# KonamiSCC_Replacement.net
KiCad netlist of a schematic drawn in EAGLE
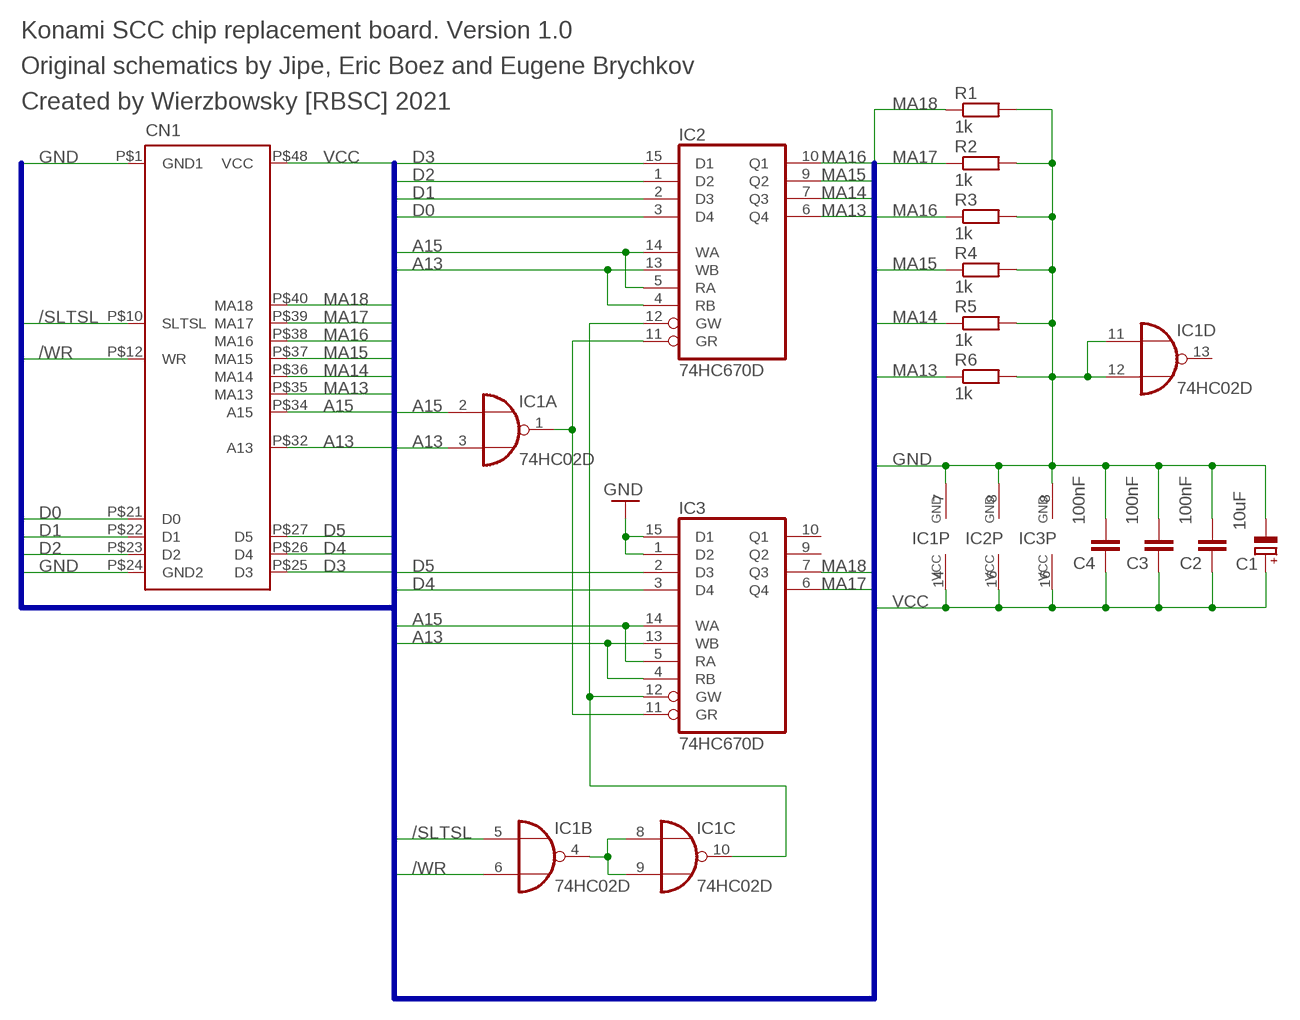
[diagram p0: schematic, sheet 1]

(export (version "E")
  (design (tool "Eeschema 10.0.6"))
  (components
    (comp (ref "C1")
      (value "10uF")
      (footprint "eagle-import:SMC_C")
      (libsource (lib "eagle-import") (part "CPOL-EUSMCC"))
    )
    (comp (ref "C2")
      (value "100nF")
      (footprint "eagle-import:C0805")
      (libsource (lib "eagle-import") (part "C-EUC0805"))
    )
    (comp (ref "C3")
      (value "100nF")
      (footprint "eagle-import:C0805")
      (libsource (lib "eagle-import") (part "C-EUC0805"))
    )
    (comp (ref "C4")
      (value "100nF")
      (footprint "eagle-import:C0805")
      (libsource (lib "eagle-import") (part "C-EUC0805"))
    )
    (comp (ref "CN1")
      (value "2212P003_PLACEHOLDERP")
      (footprint "eagle-import:DIP48")
      (libsource (lib "eagle-import") (part "2212P003_PLACEHOLDERP"))
    )
    (comp (ref "IC1")
      (value "74HC02D")
      (footprint "eagle-import:SO14")
      (libsource (lib "eagle-import") (part "7402DHC"))
    )
    (comp (ref "IC2")
      (value "74HC670D")
      (footprint "eagle-import:SO16")
      (libsource (lib "eagle-import") (part "74670DHC"))
    )
    (comp (ref "IC3")
      (value "74HC670D")
      (footprint "eagle-import:SO16")
      (libsource (lib "eagle-import") (part "74670DHC"))
    )
    (comp (ref "R1")
      (value "1k")
      (footprint "eagle-import:M0805")
      (libsource (lib "eagle-import") (part "R-EU_M0805"))
    )
    (comp (ref "R2")
      (value "1k")
      (footprint "eagle-import:M0805")
      (libsource (lib "eagle-import") (part "R-EU_M0805"))
    )
    (comp (ref "R3")
      (value "1k")
      (footprint "eagle-import:M0805")
      (libsource (lib "eagle-import") (part "R-EU_M0805"))
    )
    (comp (ref "R4")
      (value "1k")
      (footprint "eagle-import:M0805")
      (libsource (lib "eagle-import") (part "R-EU_M0805"))
    )
    (comp (ref "R5")
      (value "1k")
      (footprint "eagle-import:M0805")
      (libsource (lib "eagle-import") (part "R-EU_M0805"))
    )
    (comp (ref "R6")
      (value "1k")
      (footprint "eagle-import:M0805")
      (libsource (lib "eagle-import") (part "R-EU_M0805"))
    )
  )
  (nets
    (net (code "1") (name "/A13") (class "Default")
      (node (ref "CN1") (pin "P$32") (pinfunction "A13_P$32") (pintype "bidirectional"))
      (node (ref "IC1") (pin "3") (pinfunction "I1_3") (pintype "input"))
      (node (ref "IC2") (pin "13") (pinfunction "WB_13") (pintype "input"))
      (node (ref "IC2") (pin "4") (pinfunction "RB_4") (pintype "input"))
      (node (ref "IC3") (pin "13") (pinfunction "WB_13") (pintype "input"))
      (node (ref "IC3") (pin "4") (pinfunction "RB_4") (pintype "input"))
    )
    (net (code "2") (name "/A15") (class "Default")
      (node (ref "CN1") (pin "P$34") (pinfunction "A15_P$34") (pintype "bidirectional"))
      (node (ref "IC1") (pin "2") (pinfunction "I0_2") (pintype "input"))
      (node (ref "IC2") (pin "14") (pinfunction "WA_14") (pintype "input"))
      (node (ref "IC2") (pin "5") (pinfunction "RA_5") (pintype "input"))
      (node (ref "IC3") (pin "14") (pinfunction "WA_14") (pintype "input"))
      (node (ref "IC3") (pin "5") (pinfunction "RA_5") (pintype "input"))
    )
    (net (code "3") (name "/D0") (class "Default")
      (node (ref "CN1") (pin "P$21") (pinfunction "D0_P$21") (pintype "bidirectional"))
      (node (ref "IC2") (pin "3") (pinfunction "D4_3") (pintype "input"))
    )
    (net (code "4") (name "/D1") (class "Default")
      (node (ref "CN1") (pin "P$22") (pinfunction "D1_P$22") (pintype "bidirectional"))
      (node (ref "IC2") (pin "2") (pinfunction "D3_2") (pintype "input"))
    )
    (net (code "5") (name "/D2") (class "Default")
      (node (ref "CN1") (pin "P$23") (pinfunction "D2_P$23") (pintype "bidirectional"))
      (node (ref "IC2") (pin "1") (pinfunction "D2_1") (pintype "input"))
    )
    (net (code "6") (name "/D3") (class "Default")
      (node (ref "CN1") (pin "P$25") (pinfunction "D3_P$25") (pintype "bidirectional"))
      (node (ref "IC2") (pin "15") (pinfunction "D1_15") (pintype "input"))
    )
    (net (code "7") (name "/D4") (class "Default")
      (node (ref "CN1") (pin "P$26") (pinfunction "D4_P$26") (pintype "bidirectional"))
      (node (ref "IC3") (pin "3") (pinfunction "D4_3") (pintype "input"))
    )
    (net (code "8") (name "/D5") (class "Default")
      (node (ref "CN1") (pin "P$27") (pinfunction "D5_P$27") (pintype "bidirectional"))
      (node (ref "IC3") (pin "2") (pinfunction "D3_2") (pintype "input"))
    )
    (net (code "9") (name "/MA13") (class "Default")
      (node (ref "CN1") (pin "P$35") (pinfunction "MA13_P$35") (pintype "bidirectional"))
      (node (ref "IC2") (pin "6") (pinfunction "Q4_6") (pintype "tri_state"))
      (node (ref "R6") (pin "1") (pinfunction "1_1") (pintype "passive"))
    )
    (net (code "10") (name "/MA14") (class "Default")
      (node (ref "CN1") (pin "P$36") (pinfunction "MA14_P$36") (pintype "bidirectional"))
      (node (ref "IC2") (pin "7") (pinfunction "Q3_7") (pintype "tri_state"))
      (node (ref "R5") (pin "1") (pinfunction "1_1") (pintype "passive"))
    )
    (net (code "11") (name "/MA15") (class "Default")
      (node (ref "CN1") (pin "P$37") (pinfunction "MA15_P$37") (pintype "bidirectional"))
      (node (ref "IC2") (pin "9") (pinfunction "Q2_9") (pintype "tri_state"))
      (node (ref "R4") (pin "1") (pinfunction "1_1") (pintype "passive"))
    )
    (net (code "12") (name "/MA16") (class "Default")
      (node (ref "CN1") (pin "P$38") (pinfunction "MA16_P$38") (pintype "bidirectional"))
      (node (ref "IC2") (pin "10") (pinfunction "Q1_10") (pintype "tri_state"))
      (node (ref "R3") (pin "1") (pinfunction "1_1") (pintype "passive"))
    )
    (net (code "13") (name "/MA17") (class "Default")
      (node (ref "CN1") (pin "P$39") (pinfunction "MA17_P$39") (pintype "bidirectional"))
      (node (ref "IC3") (pin "6") (pinfunction "Q4_6") (pintype "tri_state"))
      (node (ref "R2") (pin "1") (pinfunction "1_1") (pintype "passive"))
    )
    (net (code "14") (name "/MA18") (class "Default")
      (node (ref "CN1") (pin "P$40") (pinfunction "MA18_P$40") (pintype "bidirectional"))
      (node (ref "IC3") (pin "7") (pinfunction "Q3_7") (pintype "tri_state"))
      (node (ref "R1") (pin "1") (pinfunction "1_1") (pintype "passive"))
    )
    (net (code "15") (name "/VCC") (class "Default")
      (node (ref "C1") (pin "+") (pinfunction "+_+") (pintype "passive"))
      (node (ref "C2") (pin "1") (pinfunction "1_1") (pintype "passive"))
      (node (ref "C3") (pin "1") (pinfunction "1_1") (pintype "passive"))
      (node (ref "C4") (pin "1") (pinfunction "1_1") (pintype "passive"))
      (node (ref "CN1") (pin "P$48") (pinfunction "VCC_P$48") (pintype "bidirectional"))
      (node (ref "IC1") (pin "14") (pinfunction "VCC_14") (pintype "power_in"))
      (node (ref "IC2") (pin "16") (pinfunction "VCC_16") (pintype "power_in"))
      (node (ref "IC3") (pin "16") (pinfunction "VCC_16") (pintype "power_in"))
    )
    (net (code "16") (name "/{slash}SLTSL") (class "Default")
      (node (ref "CN1") (pin "P$10") (pinfunction "SLTSL_P$10") (pintype "bidirectional"))
      (node (ref "IC1") (pin "5") (pinfunction "I0_5") (pintype "input"))
    )
    (net (code "17") (name "/{slash}WR") (class "Default")
      (node (ref "CN1") (pin "P$12") (pinfunction "WR_P$12") (pintype "bidirectional"))
      (node (ref "IC1") (pin "6") (pinfunction "I1_6") (pintype "input"))
    )
    (net (code "18") (name "GND") (class "Default")
      (node (ref "C1") (pin "-") (pinfunction "-_-") (pintype "passive"))
      (node (ref "C2") (pin "2") (pinfunction "2_2") (pintype "passive"))
      (node (ref "C3") (pin "2") (pinfunction "2_2") (pintype "passive"))
      (node (ref "C4") (pin "2") (pinfunction "2_2") (pintype "passive"))
      (node (ref "CN1") (pin "P$1") (pinfunction "GND1_P$1") (pintype "bidirectional"))
      (node (ref "CN1") (pin "P$24") (pinfunction "GND2_P$24") (pintype "bidirectional"))
      (node (ref "IC1") (pin "11") (pinfunction "I0_11") (pintype "input"))
      (node (ref "IC1") (pin "12") (pinfunction "I1_12") (pintype "input"))
      (node (ref "IC1") (pin "7") (pinfunction "GND_7") (pintype "power_in"))
      (node (ref "IC2") (pin "8") (pinfunction "GND_8") (pintype "power_in"))
      (node (ref "IC3") (pin "1") (pinfunction "D2_1") (pintype "input"))
      (node (ref "IC3") (pin "15") (pinfunction "D1_15") (pintype "input"))
      (node (ref "IC3") (pin "8") (pinfunction "GND_8") (pintype "power_in"))
      (node (ref "R1") (pin "2") (pinfunction "2_2") (pintype "passive"))
      (node (ref "R2") (pin "2") (pinfunction "2_2") (pintype "passive"))
      (node (ref "R3") (pin "2") (pinfunction "2_2") (pintype "passive"))
      (node (ref "R4") (pin "2") (pinfunction "2_2") (pintype "passive"))
      (node (ref "R5") (pin "2") (pinfunction "2_2") (pintype "passive"))
      (node (ref "R6") (pin "2") (pinfunction "2_2") (pintype "passive"))
    )
    (net (code "19") (name "Net-(IC1A-O)") (class "Default")
      (node (ref "IC1") (pin "1") (pinfunction "O_1") (pintype "output"))
      (node (ref "IC2") (pin "11") (pinfunction "GR_11") (pintype "input"))
      (node (ref "IC3") (pin "11") (pinfunction "GR_11") (pintype "input"))
    )
    (net (code "20") (name "Net-(IC1B-O)") (class "Default")
      (node (ref "IC1") (pin "4") (pinfunction "O_4") (pintype "output"))
      (node (ref "IC1") (pin "8") (pinfunction "I0_8") (pintype "input"))
      (node (ref "IC1") (pin "9") (pinfunction "I1_9") (pintype "input"))
    )
    (net (code "21") (name "Net-(IC1C-O)") (class "Default")
      (node (ref "IC1") (pin "10") (pinfunction "O_10") (pintype "output"))
      (node (ref "IC2") (pin "12") (pinfunction "GW_12") (pintype "input"))
      (node (ref "IC3") (pin "12") (pinfunction "GW_12") (pintype "input"))
    )
    (net (code "22") (name "unconnected-(IC1D-O-Pad13)") (class "Default")
      (node (ref "IC1") (pin "13") (pinfunction "O_13") (pintype "output"))
    )
    (net (code "23") (name "unconnected-(IC3A-Q1-Pad10)") (class "Default")
      (node (ref "IC3") (pin "10") (pinfunction "Q1_10") (pintype "tri_state"))
    )
    (net (code "24") (name "unconnected-(IC3A-Q2-Pad9)") (class "Default")
      (node (ref "IC3") (pin "9") (pinfunction "Q2_9") (pintype "tri_state"))
    )
  )
)
